# bootloader.net
KiCad netlist of a schematic drawn in Altium Designer
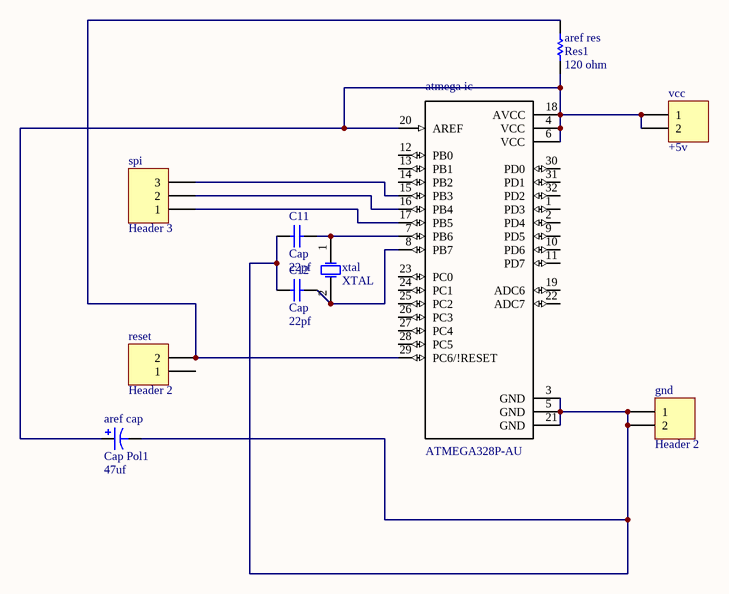
[diagram p0: bootloader.SchDoc]

(export (version "E")
  (design (tool "Eeschema 10.0.6"))
  (components
    (comp (ref "aref cap")
      (value "Cap Pol1")
      (footprint "RB7.6-15")
      (description "Polarized Capacitor (Radial)")
      (fields (field (name "ALTIUM_VALUE") "47uf") (field (name "PUBLISHER") "Altium Limited"))
      (libsource (lib "Miscellaneous Devices") (part "Cap Pol1"))
    )
    (comp (ref "aref res")
      (value "Res1")
      (footprint "AXIAL-0.3")
      (description "Resistor")
      (fields (field (name "ALTIUM_VALUE") "120 ohm") (field (name "PUBLISHER") "Altium Limited"))
      (libsource (lib "Miscellaneous Devices") (part "Res1"))
    )
    (comp (ref "atmega ic")
      (value "ATMEGA328P-AU")
      (footprint "*QFP80P900X900X120-32N")
      (description "Microcontroller Mcu, 8 Bit, Atmega, 20mhz, Tqfp-32")
      (fields (field (name "DIGI-KEY_PART_NUMBER") "ATMEGA328P-AU-ND") (field (name "MF") "Microchip"))
      (libsource (lib "ATMEGA328P-AU") (part "ATMEGA328P-AU"))
    )
    (comp (ref "C11")
      (value "Cap")
      (footprint "RAD-0.3")
      (description "Capacitor")
      (fields (field (name "ALTIUM_VALUE") "22pf") (field (name "PUBLISHER") "Altium Limited"))
      (libsource (lib "Miscellaneous Devices") (part "Cap"))
    )
    (comp (ref "C12")
      (value "Cap")
      (footprint "RAD-0.3")
      (description "Capacitor")
      (fields (field (name "ALTIUM_VALUE") "22pf") (field (name "PUBLISHER") "Altium Limited"))
      (libsource (lib "Miscellaneous Devices") (part "Cap"))
    )
    (comp (ref "gnd")
      (value "Header 2")
      (footprint "HDR1X2")
      (description "Header, 2-Pin")
      (fields (field (name "PUBLISHER") "Altium Limited"))
      (libsource (lib "Miscellaneous Connectors") (part "Header 2"))
    )
    (comp (ref "reset")
      (value "Header 2")
      (footprint "HDR1X2")
      (description "Header, 2-Pin")
      (fields (field (name "PUBLISHER") "Altium Limited"))
      (libsource (lib "") (part "Header 2_1"))
    )
    (comp (ref "spi")
      (value "Header 3")
      (footprint "HDR1X3")
      (description "Header, 3-Pin")
      (fields (field (name "PUBLISHER") "Altium Limited"))
      (libsource (lib "Miscellaneous Connectors") (part "Header 3"))
    )
    (comp (ref "vcc")
      (value "+5v")
      (footprint "HDR1X2")
      (description "Header, 2-Pin")
      (fields (field (name "PUBLISHER") "Altium Limited"))
      (libsource (lib "Miscellaneous Connectors") (part "Header 2"))
    )
    (comp (ref "xtal")
      (value "XTAL")
      (footprint "R38")
      (description "Crystal Oscillator")
      (fields (field (name "PUBLISHER") "Altium Limited"))
      (libsource (lib "Miscellaneous Devices") (part "XTAL"))
    )
  )
  (nets
    (net (code "1") (name "Net-(C11-Pad1)") (class "Default")
      (node (ref "C11") (pin "1") (pinfunction "1_1") (pintype "passive"))
      (node (ref "C12") (pin "1") (pinfunction "1_1") (pintype "passive"))
      (node (ref "aref cap") (pin "2") (pinfunction "2_2") (pintype "passive"))
      (node (ref "atmega ic") (pin "21") (pinfunction "GND_21") (pintype "power_in"))
      (node (ref "atmega ic") (pin "3") (pinfunction "GND_3") (pintype "power_in"))
      (node (ref "atmega ic") (pin "5") (pinfunction "GND_5") (pintype "power_in"))
      (node (ref "gnd") (pin "1") (pinfunction "1_1") (pintype "passive"))
      (node (ref "gnd") (pin "2") (pinfunction "2_2") (pintype "passive"))
    )
    (net (code "2") (name "Net-(atmega ic-AREF)") (class "Default")
      (node (ref "aref cap") (pin "1") (pinfunction "1_1") (pintype "passive"))
      (node (ref "aref res") (pin "1") (pinfunction "1_1") (pintype "passive"))
      (node (ref "atmega ic") (pin "18") (pinfunction "AVCC_18") (pintype "power_in"))
      (node (ref "atmega ic") (pin "20") (pinfunction "AREF_20") (pintype "input"))
      (node (ref "atmega ic") (pin "4") (pinfunction "VCC_4") (pintype "power_in"))
      (node (ref "atmega ic") (pin "6") (pinfunction "VCC_6") (pintype "power_in"))
      (node (ref "vcc") (pin "1") (pinfunction "1_1") (pintype "passive"))
      (node (ref "vcc") (pin "2") (pinfunction "2_2") (pintype "passive"))
    )
    (net (code "3") (name "Net-(atmega ic-PB3)") (class "Default")
      (node (ref "atmega ic") (pin "15") (pinfunction "PB3_15") (pintype "bidirectional"))
      (node (ref "spi") (pin "3") (pinfunction "3_3") (pintype "passive"))
    )
    (net (code "4") (name "Net-(atmega ic-PB4)") (class "Default")
      (node (ref "atmega ic") (pin "16") (pinfunction "PB4_16") (pintype "bidirectional"))
      (node (ref "spi") (pin "2") (pinfunction "2_2") (pintype "passive"))
    )
    (net (code "5") (name "Net-(atmega ic-PB5)") (class "Default")
      (node (ref "atmega ic") (pin "17") (pinfunction "PB5_17") (pintype "bidirectional"))
      (node (ref "spi") (pin "1") (pinfunction "1_1") (pintype "passive"))
    )
    (net (code "6") (name "Net-(atmega ic-PB6)") (class "Default")
      (node (ref "C11") (pin "2") (pinfunction "2_2") (pintype "passive"))
      (node (ref "atmega ic") (pin "7") (pinfunction "PB6_7") (pintype "bidirectional"))
      (node (ref "xtal") (pin "1") (pinfunction "OSC1_1") (pintype "passive"))
    )
    (net (code "7") (name "Net-(atmega ic-PB7)") (class "Default")
      (node (ref "C12") (pin "2") (pinfunction "2_2") (pintype "passive"))
      (node (ref "atmega ic") (pin "8") (pinfunction "PB7_8") (pintype "bidirectional"))
      (node (ref "xtal") (pin "2") (pinfunction "OSC2_2") (pintype "passive"))
    )
    (net (code "8") (name "Net-(atmega ic-PC6{slash}!RESET)") (class "Default")
      (node (ref "aref res") (pin "2") (pinfunction "2_2") (pintype "passive"))
      (node (ref "atmega ic") (pin "29") (pinfunction "PC6/!RESET_29") (pintype "bidirectional"))
      (node (ref "reset") (pin "2") (pinfunction "2_2") (pintype "passive"))
    )
    (net (code "9") (name "unconnected-(atmega ic-ADC6-Pad19)") (class "Default")
      (node (ref "atmega ic") (pin "19") (pinfunction "ADC6_19") (pintype "bidirectional"))
    )
    (net (code "10") (name "unconnected-(atmega ic-ADC7-Pad22)") (class "Default")
      (node (ref "atmega ic") (pin "22") (pinfunction "ADC7_22") (pintype "bidirectional"))
    )
    (net (code "11") (name "unconnected-(atmega ic-PB0-Pad12)") (class "Default")
      (node (ref "atmega ic") (pin "12") (pinfunction "PB0_12") (pintype "bidirectional"))
    )
    (net (code "12") (name "unconnected-(atmega ic-PB1-Pad13)") (class "Default")
      (node (ref "atmega ic") (pin "13") (pinfunction "PB1_13") (pintype "bidirectional"))
    )
    (net (code "13") (name "unconnected-(atmega ic-PB2-Pad14)") (class "Default")
      (node (ref "atmega ic") (pin "14") (pinfunction "PB2_14") (pintype "bidirectional"))
    )
    (net (code "14") (name "unconnected-(atmega ic-PC0-Pad23)") (class "Default")
      (node (ref "atmega ic") (pin "23") (pinfunction "PC0_23") (pintype "bidirectional"))
    )
    (net (code "15") (name "unconnected-(atmega ic-PC1-Pad24)") (class "Default")
      (node (ref "atmega ic") (pin "24") (pinfunction "PC1_24") (pintype "bidirectional"))
    )
    (net (code "16") (name "unconnected-(atmega ic-PC2-Pad25)") (class "Default")
      (node (ref "atmega ic") (pin "25") (pinfunction "PC2_25") (pintype "bidirectional"))
    )
    (net (code "17") (name "unconnected-(atmega ic-PC3-Pad26)") (class "Default")
      (node (ref "atmega ic") (pin "26") (pinfunction "PC3_26") (pintype "bidirectional"))
    )
    (net (code "18") (name "unconnected-(atmega ic-PC4-Pad27)") (class "Default")
      (node (ref "atmega ic") (pin "27") (pinfunction "PC4_27") (pintype "bidirectional"))
    )
    (net (code "19") (name "unconnected-(atmega ic-PC5-Pad28)") (class "Default")
      (node (ref "atmega ic") (pin "28") (pinfunction "PC5_28") (pintype "bidirectional"))
    )
    (net (code "20") (name "unconnected-(atmega ic-PD0-Pad30)") (class "Default")
      (node (ref "atmega ic") (pin "30") (pinfunction "PD0_30") (pintype "bidirectional"))
    )
    (net (code "21") (name "unconnected-(atmega ic-PD1-Pad31)") (class "Default")
      (node (ref "atmega ic") (pin "31") (pinfunction "PD1_31") (pintype "bidirectional"))
    )
    (net (code "22") (name "unconnected-(atmega ic-PD2-Pad32)") (class "Default")
      (node (ref "atmega ic") (pin "32") (pinfunction "PD2_32") (pintype "bidirectional"))
    )
    (net (code "23") (name "unconnected-(atmega ic-PD3-Pad1)") (class "Default")
      (node (ref "atmega ic") (pin "1") (pinfunction "PD3_1") (pintype "bidirectional"))
    )
    (net (code "24") (name "unconnected-(atmega ic-PD4-Pad2)") (class "Default")
      (node (ref "atmega ic") (pin "2") (pinfunction "PD4_2") (pintype "bidirectional"))
    )
    (net (code "25") (name "unconnected-(atmega ic-PD5-Pad9)") (class "Default")
      (node (ref "atmega ic") (pin "9") (pinfunction "PD5_9") (pintype "bidirectional"))
    )
    (net (code "26") (name "unconnected-(atmega ic-PD6-Pad10)") (class "Default")
      (node (ref "atmega ic") (pin "10") (pinfunction "PD6_10") (pintype "bidirectional"))
    )
    (net (code "27") (name "unconnected-(atmega ic-PD7-Pad11)") (class "Default")
      (node (ref "atmega ic") (pin "11") (pinfunction "PD7_11") (pintype "bidirectional"))
    )
    (net (code "28") (name "unconnected-(reset-Pad1)") (class "Default")
      (node (ref "reset") (pin "1") (pinfunction "1_1") (pintype "passive"))
    )
  )
)
